# Mateusz_Kost.net
KiCad netlist of a schematic drawn in EAGLE
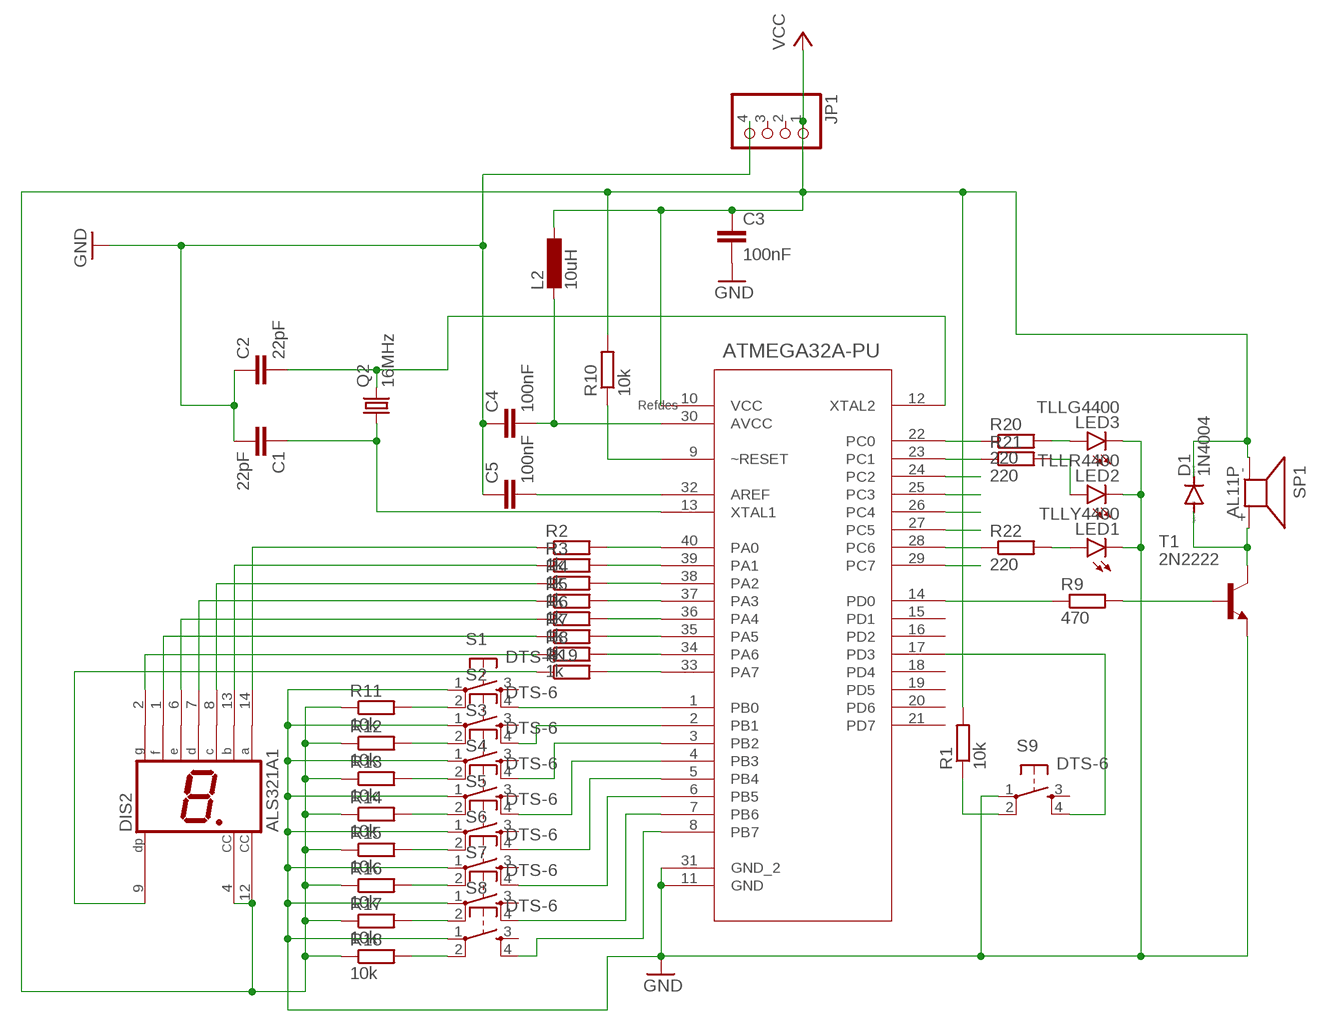
[diagram p0: schematic, sheet 1]

(export (version "E")
  (design (tool "Eeschema 10.0.6"))
  (components
    (comp (ref "C1")
      (value "22pF")
      (footprint "eagle-import:C2.5-2")
      (libsource (lib "eagle-import") (part "C2.5/2"))
    )
    (comp (ref "C2")
      (value "22pF")
      (footprint "eagle-import:C2.5-2")
      (libsource (lib "eagle-import") (part "C2.5/2"))
    )
    (comp (ref "C3")
      (value "100nF")
      (footprint "eagle-import:C2.5-2")
      (libsource (lib "eagle-import") (part "C2.5/2"))
    )
    (comp (ref "C4")
      (value "100nF")
      (footprint "eagle-import:C2.5-2")
      (libsource (lib "eagle-import") (part "C2.5/2"))
    )
    (comp (ref "C5")
      (value "100nF")
      (footprint "eagle-import:C2.5-2")
      (libsource (lib "eagle-import") (part "C2.5/2"))
    )
    (comp (ref "D1")
      (value "1N4004")
      (footprint "eagle-import:DO41-10")
      (libsource (lib "eagle-import") (part "1N4004"))
    )
    (comp (ref "DIS2")
      (value "ALS321A1")
      (footprint "eagle-import:ALS321A1")
      (libsource (lib "eagle-import") (part "ALS321A1"))
    )
    (comp (ref "JP1")
      (value "PINHD-1X4")
      (footprint "eagle-import:1X04")
      (libsource (lib "eagle-import") (part "PINHD-1X4"))
    )
    (comp (ref "L2")
      (value "10uH")
      (footprint "eagle-import:0204_5")
      (libsource (lib "eagle-import") (part "L-EU0204/5"))
    )
    (comp (ref "LED1")
      (value "TLLY4400")
      (footprint "eagle-import:LED3MM")
      (fields (field (name "MF") "VISHAY SEMICONDUCTOR"))
      (libsource (lib "eagle-import") (part "TLLY4400"))
    )
    (comp (ref "LED2")
      (value "TLLR4400")
      (footprint "eagle-import:LED3MM")
      (fields (field (name "MF") "VISHAY SEMICONDUCTOR"))
      (libsource (lib "eagle-import") (part "TLLR4400"))
    )
    (comp (ref "LED3")
      (value "TLLG4400")
      (footprint "eagle-import:LED3MM")
      (fields (field (name "MF") "VISHAY SEMICONDUCTOR"))
      (libsource (lib "eagle-import") (part "TLLG4400"))
    )
    (comp (ref "Q2")
      (value "16MHz")
      (footprint "eagle-import:HC49_S")
      (libsource (lib "eagle-import") (part "CRYSTALHC49S"))
    )
    (comp (ref "R1")
      (value "10k")
      (footprint "eagle-import:0204_7")
      (libsource (lib "eagle-import") (part "R-EU_0204/7"))
    )
    (comp (ref "R2")
      (value "1k")
      (footprint "eagle-import:0204_7")
      (libsource (lib "eagle-import") (part "R-EU_0204/7"))
    )
    (comp (ref "R3")
      (value "1k")
      (footprint "eagle-import:0204_7")
      (libsource (lib "eagle-import") (part "R-EU_0204/7"))
    )
    (comp (ref "R4")
      (value "1k")
      (footprint "eagle-import:0204_7")
      (libsource (lib "eagle-import") (part "R-EU_0204/7"))
    )
    (comp (ref "R5")
      (value "1k")
      (footprint "eagle-import:0204_7")
      (libsource (lib "eagle-import") (part "R-EU_0204/7"))
    )
    (comp (ref "R6")
      (value "1k")
      (footprint "eagle-import:0204_7")
      (libsource (lib "eagle-import") (part "R-EU_0204/7"))
    )
    (comp (ref "R7")
      (value "1k")
      (footprint "eagle-import:0204_7")
      (libsource (lib "eagle-import") (part "R-EU_0204/7"))
    )
    (comp (ref "R8")
      (value "1k")
      (footprint "eagle-import:0204_7")
      (libsource (lib "eagle-import") (part "R-EU_0204/7"))
    )
    (comp (ref "R9")
      (value "470")
      (footprint "eagle-import:0204_7")
      (libsource (lib "eagle-import") (part "R-EU_0204/7"))
    )
    (comp (ref "R10")
      (value "10k")
      (footprint "eagle-import:0204_7")
      (libsource (lib "eagle-import") (part "R-EU_0204/7"))
    )
    (comp (ref "R11")
      (value "10k")
      (footprint "eagle-import:0204_7")
      (libsource (lib "eagle-import") (part "R-EU_0204/7"))
    )
    (comp (ref "R12")
      (value "10k")
      (footprint "eagle-import:0204_7")
      (libsource (lib "eagle-import") (part "R-EU_0204/7"))
    )
    (comp (ref "R13")
      (value "10k")
      (footprint "eagle-import:0204_7")
      (libsource (lib "eagle-import") (part "R-EU_0204/7"))
    )
    (comp (ref "R14")
      (value "10k")
      (footprint "eagle-import:0204_7")
      (libsource (lib "eagle-import") (part "R-EU_0204/7"))
    )
    (comp (ref "R15")
      (value "10k")
      (footprint "eagle-import:0204_7")
      (libsource (lib "eagle-import") (part "R-EU_0204/7"))
    )
    (comp (ref "R16")
      (value "10k")
      (footprint "eagle-import:0204_7")
      (libsource (lib "eagle-import") (part "R-EU_0204/7"))
    )
    (comp (ref "R17")
      (value "10k")
      (footprint "eagle-import:0204_7")
      (libsource (lib "eagle-import") (part "R-EU_0204/7"))
    )
    (comp (ref "R18")
      (value "10k")
      (footprint "eagle-import:0204_7")
      (libsource (lib "eagle-import") (part "R-EU_0204/7"))
    )
    (comp (ref "R19")
      (value "1k")
      (footprint "eagle-import:0204_7")
      (libsource (lib "eagle-import") (part "R-EU_0204/7"))
    )
    (comp (ref "R20")
      (value "220")
      (footprint "eagle-import:0204_7")
      (libsource (lib "eagle-import") (part "R-EU_0204/7"))
    )
    (comp (ref "R21")
      (value "220")
      (footprint "eagle-import:0204_7")
      (libsource (lib "eagle-import") (part "R-EU_0204/7"))
    )
    (comp (ref "R22")
      (value "220")
      (footprint "eagle-import:0204_7")
      (libsource (lib "eagle-import") (part "R-EU_0204/7"))
    )
    (comp (ref "S1")
      (value "DTS-6")
      (footprint "eagle-import:DTS-6")
      (libsource (lib "eagle-import") (part "DTS-6"))
    )
    (comp (ref "S2")
      (value "DTS-6")
      (footprint "eagle-import:DTS-6")
      (libsource (lib "eagle-import") (part "DTS-6"))
    )
    (comp (ref "S3")
      (value "DTS-6")
      (footprint "eagle-import:DTS-6")
      (libsource (lib "eagle-import") (part "DTS-6"))
    )
    (comp (ref "S4")
      (value "DTS-6")
      (footprint "eagle-import:DTS-6")
      (libsource (lib "eagle-import") (part "DTS-6"))
    )
    (comp (ref "S5")
      (value "DTS-6")
      (footprint "eagle-import:DTS-6")
      (libsource (lib "eagle-import") (part "DTS-6"))
    )
    (comp (ref "S6")
      (value "DTS-6")
      (footprint "eagle-import:DTS-6")
      (libsource (lib "eagle-import") (part "DTS-6"))
    )
    (comp (ref "S7")
      (value "DTS-6")
      (footprint "eagle-import:DTS-6")
      (libsource (lib "eagle-import") (part "DTS-6"))
    )
    (comp (ref "S8")
      (value "DTS-6")
      (footprint "eagle-import:DTS-6")
      (libsource (lib "eagle-import") (part "DTS-6"))
    )
    (comp (ref "S9")
      (value "DTS-6")
      (footprint "eagle-import:DTS-6")
      (libsource (lib "eagle-import") (part "DTS-6"))
    )
    (comp (ref "SP1")
      (value "AL11P")
      (footprint "eagle-import:AL11P")
      (libsource (lib "eagle-import") (part "AL11P"))
    )
    (comp (ref "T1")
      (value "2N2222")
      (footprint "eagle-import:TO18")
      (libsource (lib "eagle-import") (part "2N2222"))
    )
    (comp (ref "U1")
      (value "ATMEGA32A-PU")
      (footprint "eagle-import:DIP254P1524X482-40")
      (fields (field (name "MF") "Microchip"))
      (libsource (lib "eagle-import") (part "ATMEGA32A-PU"))
    )
  )
  (nets
    (net (code "1") (name "GND") (class "Default")
      (node (ref "C1") (pin "2") (pinfunction "2_2") (pintype "passive"))
      (node (ref "C2") (pin "1") (pinfunction "1_1") (pintype "passive"))
      (node (ref "C3") (pin "2") (pinfunction "2_2") (pintype "passive"))
      (node (ref "C4") (pin "1") (pinfunction "1_1") (pintype "passive"))
      (node (ref "C5") (pin "1") (pinfunction "1_1") (pintype "passive"))
      (node (ref "JP1") (pin "4") (pinfunction "4_4") (pintype "passive"))
      (node (ref "LED1") (pin "K") (pinfunction "C_K") (pintype "passive"))
      (node (ref "LED2") (pin "K") (pinfunction "C_K") (pintype "passive"))
      (node (ref "LED3") (pin "K") (pinfunction "C_K") (pintype "passive"))
      (node (ref "S1") (pin "1") (pinfunction "1_1") (pintype "passive"))
      (node (ref "S2") (pin "1") (pinfunction "1_1") (pintype "passive"))
      (node (ref "S3") (pin "1") (pinfunction "1_1") (pintype "passive"))
      (node (ref "S4") (pin "1") (pinfunction "1_1") (pintype "passive"))
      (node (ref "S5") (pin "1") (pinfunction "1_1") (pintype "passive"))
      (node (ref "S6") (pin "1") (pinfunction "1_1") (pintype "passive"))
      (node (ref "S7") (pin "1") (pinfunction "1_1") (pintype "passive"))
      (node (ref "S8") (pin "1") (pinfunction "1_1") (pintype "passive"))
      (node (ref "S9") (pin "1") (pinfunction "1_1") (pintype "passive"))
      (node (ref "T1") (pin "1") (pinfunction "E_1") (pintype "passive"))
      (node (ref "U1") (pin "11") (pinfunction "GND_11") (pintype "passive"))
      (node (ref "U1") (pin "31") (pinfunction "GND_2_31") (pintype "passive"))
    )
    (net (code "2") (name "Net-(DIS2-A)") (class "Default")
      (node (ref "DIS2") (pin "14") (pinfunction "A_14") (pintype "passive"))
      (node (ref "R2") (pin "1") (pinfunction "1_1") (pintype "passive"))
    )
    (net (code "3") (name "Net-(DIS2-B)") (class "Default")
      (node (ref "DIS2") (pin "13") (pinfunction "B_13") (pintype "passive"))
      (node (ref "R3") (pin "1") (pinfunction "1_1") (pintype "passive"))
    )
    (net (code "4") (name "Net-(DIS2-C)") (class "Default")
      (node (ref "DIS2") (pin "8") (pinfunction "C_8") (pintype "passive"))
      (node (ref "R4") (pin "1") (pinfunction "1_1") (pintype "passive"))
    )
    (net (code "5") (name "Net-(DIS2-D)") (class "Default")
      (node (ref "DIS2") (pin "7") (pinfunction "D_7") (pintype "passive"))
      (node (ref "R5") (pin "1") (pinfunction "1_1") (pintype "passive"))
    )
    (net (code "6") (name "Net-(DIS2-DP)") (class "Default")
      (node (ref "DIS2") (pin "9") (pinfunction "DP_9") (pintype "passive"))
      (node (ref "R19") (pin "1") (pinfunction "1_1") (pintype "passive"))
    )
    (net (code "7") (name "Net-(DIS2-E)") (class "Default")
      (node (ref "DIS2") (pin "6") (pinfunction "E_6") (pintype "passive"))
      (node (ref "R6") (pin "1") (pinfunction "1_1") (pintype "passive"))
    )
    (net (code "8") (name "Net-(DIS2-F)") (class "Default")
      (node (ref "DIS2") (pin "1") (pinfunction "F_1") (pintype "passive"))
      (node (ref "R7") (pin "1") (pinfunction "1_1") (pintype "passive"))
    )
    (net (code "9") (name "Net-(DIS2-G)") (class "Default")
      (node (ref "DIS2") (pin "2") (pinfunction "G_2") (pintype "passive"))
      (node (ref "R8") (pin "1") (pinfunction "1_1") (pintype "passive"))
    )
    (net (code "10") (name "Net-(LED1-PadA)") (class "Default")
      (node (ref "LED1") (pin "A") (pinfunction "A_A") (pintype "passive"))
      (node (ref "R22") (pin "2") (pinfunction "2_2") (pintype "passive"))
    )
    (net (code "11") (name "Net-(LED2-PadA)") (class "Default")
      (node (ref "LED2") (pin "A") (pinfunction "A_A") (pintype "passive"))
      (node (ref "R21") (pin "2") (pinfunction "2_2") (pintype "passive"))
    )
    (net (code "12") (name "Net-(LED3-PadA)") (class "Default")
      (node (ref "LED3") (pin "A") (pinfunction "A_A") (pintype "passive"))
      (node (ref "R20") (pin "2") (pinfunction "2_2") (pintype "passive"))
    )
    (net (code "13") (name "Net-(R1-Pad1)") (class "Default")
      (node (ref "R1") (pin "1") (pinfunction "1_1") (pintype "passive"))
      (node (ref "S9") (pin "2") (pinfunction "2_2") (pintype "passive"))
    )
    (net (code "14") (name "Net-(R11-Pad2)") (class "Default")
      (node (ref "R11") (pin "2") (pinfunction "2_2") (pintype "passive"))
      (node (ref "S1") (pin "2") (pinfunction "2_2") (pintype "passive"))
    )
    (net (code "15") (name "Net-(R12-Pad2)") (class "Default")
      (node (ref "R12") (pin "2") (pinfunction "2_2") (pintype "passive"))
      (node (ref "S2") (pin "2") (pinfunction "2_2") (pintype "passive"))
    )
    (net (code "16") (name "Net-(R13-Pad2)") (class "Default")
      (node (ref "R13") (pin "2") (pinfunction "2_2") (pintype "passive"))
      (node (ref "S3") (pin "2") (pinfunction "2_2") (pintype "passive"))
    )
    (net (code "17") (name "Net-(R14-Pad2)") (class "Default")
      (node (ref "R14") (pin "2") (pinfunction "2_2") (pintype "passive"))
      (node (ref "S4") (pin "2") (pinfunction "2_2") (pintype "passive"))
    )
    (net (code "18") (name "Net-(R15-Pad2)") (class "Default")
      (node (ref "R15") (pin "2") (pinfunction "2_2") (pintype "passive"))
      (node (ref "S5") (pin "2") (pinfunction "2_2") (pintype "passive"))
    )
    (net (code "19") (name "Net-(R16-Pad2)") (class "Default")
      (node (ref "R16") (pin "2") (pinfunction "2_2") (pintype "passive"))
      (node (ref "S6") (pin "2") (pinfunction "2_2") (pintype "passive"))
    )
    (net (code "20") (name "Net-(R17-Pad2)") (class "Default")
      (node (ref "R17") (pin "2") (pinfunction "2_2") (pintype "passive"))
      (node (ref "S7") (pin "2") (pinfunction "2_2") (pintype "passive"))
    )
    (net (code "21") (name "Net-(R18-Pad2)") (class "Default")
      (node (ref "R18") (pin "2") (pinfunction "2_2") (pintype "passive"))
      (node (ref "S8") (pin "2") (pinfunction "2_2") (pintype "passive"))
    )
    (net (code "22") (name "Net-(SP1-2)") (class "Default")
      (node (ref "D1") (pin "A") (pinfunction "A_A") (pintype "passive"))
      (node (ref "SP1") (pin "+") (pinfunction "2_+") (pintype "passive"))
      (node (ref "T1") (pin "3") (pinfunction "C_3") (pintype "passive"))
    )
    (net (code "23") (name "Net-(T1-B)") (class "Default")
      (node (ref "R9") (pin "2") (pinfunction "2_2") (pintype "passive"))
      (node (ref "T1") (pin "2") (pinfunction "B_2") (pintype "passive"))
    )
    (net (code "24") (name "Net-(U1-AREF)") (class "Default")
      (node (ref "C5") (pin "2") (pinfunction "2_2") (pintype "passive"))
      (node (ref "U1") (pin "32") (pinfunction "AREF_32") (pintype "input"))
    )
    (net (code "25") (name "Net-(U1-AVCC)") (class "Default")
      (node (ref "C4") (pin "2") (pinfunction "2_2") (pintype "passive"))
      (node (ref "L2") (pin "2") (pinfunction "2_2") (pintype "passive"))
      (node (ref "U1") (pin "30") (pinfunction "AVCC_30") (pintype "power_in"))
    )
    (net (code "26") (name "Net-(U1-PA0)") (class "Default")
      (node (ref "R2") (pin "2") (pinfunction "2_2") (pintype "passive"))
      (node (ref "U1") (pin "40") (pinfunction "PA0_40") (pintype "bidirectional"))
    )
    (net (code "27") (name "Net-(U1-PA1)") (class "Default")
      (node (ref "R3") (pin "2") (pinfunction "2_2") (pintype "passive"))
      (node (ref "U1") (pin "39") (pinfunction "PA1_39") (pintype "bidirectional"))
    )
    (net (code "28") (name "Net-(U1-PA2)") (class "Default")
      (node (ref "R4") (pin "2") (pinfunction "2_2") (pintype "passive"))
      (node (ref "U1") (pin "38") (pinfunction "PA2_38") (pintype "bidirectional"))
    )
    (net (code "29") (name "Net-(U1-PA3)") (class "Default")
      (node (ref "R5") (pin "2") (pinfunction "2_2") (pintype "passive"))
      (node (ref "U1") (pin "37") (pinfunction "PA3_37") (pintype "bidirectional"))
    )
    (net (code "30") (name "Net-(U1-PA4)") (class "Default")
      (node (ref "R6") (pin "2") (pinfunction "2_2") (pintype "passive"))
      (node (ref "U1") (pin "36") (pinfunction "PA4_36") (pintype "bidirectional"))
    )
    (net (code "31") (name "Net-(U1-PA5)") (class "Default")
      (node (ref "R7") (pin "2") (pinfunction "2_2") (pintype "passive"))
      (node (ref "U1") (pin "35") (pinfunction "PA5_35") (pintype "bidirectional"))
    )
    (net (code "32") (name "Net-(U1-PA6)") (class "Default")
      (node (ref "R8") (pin "2") (pinfunction "2_2") (pintype "passive"))
      (node (ref "U1") (pin "34") (pinfunction "PA6_34") (pintype "bidirectional"))
    )
    (net (code "33") (name "Net-(U1-PA7)") (class "Default")
      (node (ref "R19") (pin "2") (pinfunction "2_2") (pintype "passive"))
      (node (ref "U1") (pin "33") (pinfunction "PA7_33") (pintype "bidirectional"))
    )
    (net (code "34") (name "Net-(U1-PB0)") (class "Default")
      (node (ref "S1") (pin "4") (pinfunction "4_4") (pintype "passive"))
      (node (ref "U1") (pin "1") (pinfunction "PB0_1") (pintype "bidirectional"))
    )
    (net (code "35") (name "Net-(U1-PB1)") (class "Default")
      (node (ref "S2") (pin "4") (pinfunction "4_4") (pintype "passive"))
      (node (ref "U1") (pin "2") (pinfunction "PB1_2") (pintype "bidirectional"))
    )
    (net (code "36") (name "Net-(U1-PB2)") (class "Default")
      (node (ref "S3") (pin "4") (pinfunction "4_4") (pintype "passive"))
      (node (ref "U1") (pin "3") (pinfunction "PB2_3") (pintype "bidirectional"))
    )
    (net (code "37") (name "Net-(U1-PB3)") (class "Default")
      (node (ref "S4") (pin "4") (pinfunction "4_4") (pintype "passive"))
      (node (ref "U1") (pin "4") (pinfunction "PB3_4") (pintype "bidirectional"))
    )
    (net (code "38") (name "Net-(U1-PB4)") (class "Default")
      (node (ref "S5") (pin "4") (pinfunction "4_4") (pintype "passive"))
      (node (ref "U1") (pin "5") (pinfunction "PB4_5") (pintype "bidirectional"))
    )
    (net (code "39") (name "Net-(U1-PB5)") (class "Default")
      (node (ref "S6") (pin "4") (pinfunction "4_4") (pintype "passive"))
      (node (ref "U1") (pin "6") (pinfunction "PB5_6") (pintype "bidirectional"))
    )
    (net (code "40") (name "Net-(U1-PB6)") (class "Default")
      (node (ref "S7") (pin "4") (pinfunction "4_4") (pintype "passive"))
      (node (ref "U1") (pin "7") (pinfunction "PB6_7") (pintype "bidirectional"))
    )
    (net (code "41") (name "Net-(U1-PB7)") (class "Default")
      (node (ref "S8") (pin "4") (pinfunction "4_4") (pintype "passive"))
      (node (ref "U1") (pin "8") (pinfunction "PB7_8") (pintype "bidirectional"))
    )
    (net (code "42") (name "Net-(U1-PC0)") (class "Default")
      (node (ref "R20") (pin "1") (pinfunction "1_1") (pintype "passive"))
      (node (ref "U1") (pin "22") (pinfunction "PC0_22") (pintype "bidirectional"))
    )
    (net (code "43") (name "Net-(U1-PC1)") (class "Default")
      (node (ref "R21") (pin "1") (pinfunction "1_1") (pintype "passive"))
      (node (ref "U1") (pin "23") (pinfunction "PC1_23") (pintype "bidirectional"))
    )
    (net (code "44") (name "Net-(U1-PC6)") (class "Default")
      (node (ref "R22") (pin "1") (pinfunction "1_1") (pintype "passive"))
      (node (ref "U1") (pin "28") (pinfunction "PC6_28") (pintype "bidirectional"))
    )
    (net (code "45") (name "Net-(U1-PD0)") (class "Default")
      (node (ref "R9") (pin "1") (pinfunction "1_1") (pintype "passive"))
      (node (ref "U1") (pin "14") (pinfunction "PD0_14") (pintype "bidirectional"))
    )
    (net (code "46") (name "Net-(U1-PD3)") (class "Default")
      (node (ref "S9") (pin "4") (pinfunction "4_4") (pintype "passive"))
      (node (ref "U1") (pin "17") (pinfunction "PD3_17") (pintype "bidirectional"))
    )
    (net (code "47") (name "Net-(U1-XTAL1)") (class "Default")
      (node (ref "C1") (pin "1") (pinfunction "1_1") (pintype "passive"))
      (node (ref "Q2") (pin "1") (pinfunction "1_1") (pintype "passive"))
      (node (ref "U1") (pin "13") (pinfunction "XTAL1_13") (pintype "input"))
    )
    (net (code "48") (name "Net-(U1-XTAL2)") (class "Default")
      (node (ref "C2") (pin "2") (pinfunction "2_2") (pintype "passive"))
      (node (ref "Q2") (pin "2") (pinfunction "2_2") (pintype "passive"))
      (node (ref "U1") (pin "12") (pinfunction "XTAL2_12") (pintype "output"))
    )
    (net (code "49") (name "Net-(U1-~{RESET})") (class "Default")
      (node (ref "R10") (pin "1") (pinfunction "1_1") (pintype "passive"))
      (node (ref "U1") (pin "9") (pinfunction "~{RESET}_9") (pintype "input"))
    )
    (net (code "50") (name "VCC") (class "Default")
      (node (ref "C3") (pin "1") (pinfunction "1_1") (pintype "passive"))
      (node (ref "D1") (pin "C") (pinfunction "C_C") (pintype "passive"))
      (node (ref "DIS2") (pin "12") (pinfunction "CC_12") (pintype "passive"))
      (node (ref "DIS2") (pin "4") (pinfunction "CC_4") (pintype "passive"))
      (node (ref "JP1") (pin "1") (pinfunction "1_1") (pintype "passive"))
      (node (ref "L2") (pin "1") (pinfunction "1_1") (pintype "passive"))
      (node (ref "R1") (pin "2") (pinfunction "2_2") (pintype "passive"))
      (node (ref "R10") (pin "2") (pinfunction "2_2") (pintype "passive"))
      (node (ref "R11") (pin "1") (pinfunction "1_1") (pintype "passive"))
      (node (ref "R12") (pin "1") (pinfunction "1_1") (pintype "passive"))
      (node (ref "R13") (pin "1") (pinfunction "1_1") (pintype "passive"))
      (node (ref "R14") (pin "1") (pinfunction "1_1") (pintype "passive"))
      (node (ref "R15") (pin "1") (pinfunction "1_1") (pintype "passive"))
      (node (ref "R16") (pin "1") (pinfunction "1_1") (pintype "passive"))
      (node (ref "R17") (pin "1") (pinfunction "1_1") (pintype "passive"))
      (node (ref "R18") (pin "1") (pinfunction "1_1") (pintype "passive"))
      (node (ref "SP1") (pin "-") (pinfunction "1_-") (pintype "passive"))
      (node (ref "U1") (pin "10") (pinfunction "VCC_10") (pintype "power_in"))
    )
    (net (code "51") (name "unconnected-(JP1-Pad2)") (class "Default")
      (node (ref "JP1") (pin "2") (pinfunction "2_2") (pintype "passive"))
    )
    (net (code "52") (name "unconnected-(JP1-Pad3)") (class "Default")
      (node (ref "JP1") (pin "3") (pinfunction "3_3") (pintype "passive"))
    )
    (net (code "53") (name "unconnected-(S1-Pad3)") (class "Default")
      (node (ref "S1") (pin "3") (pinfunction "3_3") (pintype "passive"))
    )
    (net (code "54") (name "unconnected-(S2-Pad3)") (class "Default")
      (node (ref "S2") (pin "3") (pinfunction "3_3") (pintype "passive"))
    )
    (net (code "55") (name "unconnected-(S3-Pad3)") (class "Default")
      (node (ref "S3") (pin "3") (pinfunction "3_3") (pintype "passive"))
    )
    (net (code "56") (name "unconnected-(S4-Pad3)") (class "Default")
      (node (ref "S4") (pin "3") (pinfunction "3_3") (pintype "passive"))
    )
    (net (code "57") (name "unconnected-(S5-Pad3)") (class "Default")
      (node (ref "S5") (pin "3") (pinfunction "3_3") (pintype "passive"))
    )
    (net (code "58") (name "unconnected-(S6-Pad3)") (class "Default")
      (node (ref "S6") (pin "3") (pinfunction "3_3") (pintype "passive"))
    )
    (net (code "59") (name "unconnected-(S7-Pad3)") (class "Default")
      (node (ref "S7") (pin "3") (pinfunction "3_3") (pintype "passive"))
    )
    (net (code "60") (name "unconnected-(S8-Pad3)") (class "Default")
      (node (ref "S8") (pin "3") (pinfunction "3_3") (pintype "passive"))
    )
    (net (code "61") (name "unconnected-(S9-Pad3)") (class "Default")
      (node (ref "S9") (pin "3") (pinfunction "3_3") (pintype "passive"))
    )
    (net (code "62") (name "unconnected-(U1-PC2-Pad24)") (class "Default")
      (node (ref "U1") (pin "24") (pinfunction "PC2_24") (pintype "bidirectional"))
    )
    (net (code "63") (name "unconnected-(U1-PC3-Pad25)") (class "Default")
      (node (ref "U1") (pin "25") (pinfunction "PC3_25") (pintype "bidirectional"))
    )
    (net (code "64") (name "unconnected-(U1-PC4-Pad26)") (class "Default")
      (node (ref "U1") (pin "26") (pinfunction "PC4_26") (pintype "bidirectional"))
    )
    (net (code "65") (name "unconnected-(U1-PC5-Pad27)") (class "Default")
      (node (ref "U1") (pin "27") (pinfunction "PC5_27") (pintype "bidirectional"))
    )
    (net (code "66") (name "unconnected-(U1-PC7-Pad29)") (class "Default")
      (node (ref "U1") (pin "29") (pinfunction "PC7_29") (pintype "bidirectional"))
    )
    (net (code "67") (name "unconnected-(U1-PD1-Pad15)") (class "Default")
      (node (ref "U1") (pin "15") (pinfunction "PD1_15") (pintype "bidirectional"))
    )
    (net (code "68") (name "unconnected-(U1-PD2-Pad16)") (class "Default")
      (node (ref "U1") (pin "16") (pinfunction "PD2_16") (pintype "bidirectional"))
    )
    (net (code "69") (name "unconnected-(U1-PD4-Pad18)") (class "Default")
      (node (ref "U1") (pin "18") (pinfunction "PD4_18") (pintype "bidirectional"))
    )
    (net (code "70") (name "unconnected-(U1-PD5-Pad19)") (class "Default")
      (node (ref "U1") (pin "19") (pinfunction "PD5_19") (pintype "bidirectional"))
    )
    (net (code "71") (name "unconnected-(U1-PD6-Pad20)") (class "Default")
      (node (ref "U1") (pin "20") (pinfunction "PD6_20") (pintype "bidirectional"))
    )
    (net (code "72") (name "unconnected-(U1-PD7-Pad21)") (class "Default")
      (node (ref "U1") (pin "21") (pinfunction "PD7_21") (pintype "bidirectional"))
    )
  )
)
